# ELEC70101_TempSensors.net
KiCad netlist of a schematic drawn in EasyEDA Pro
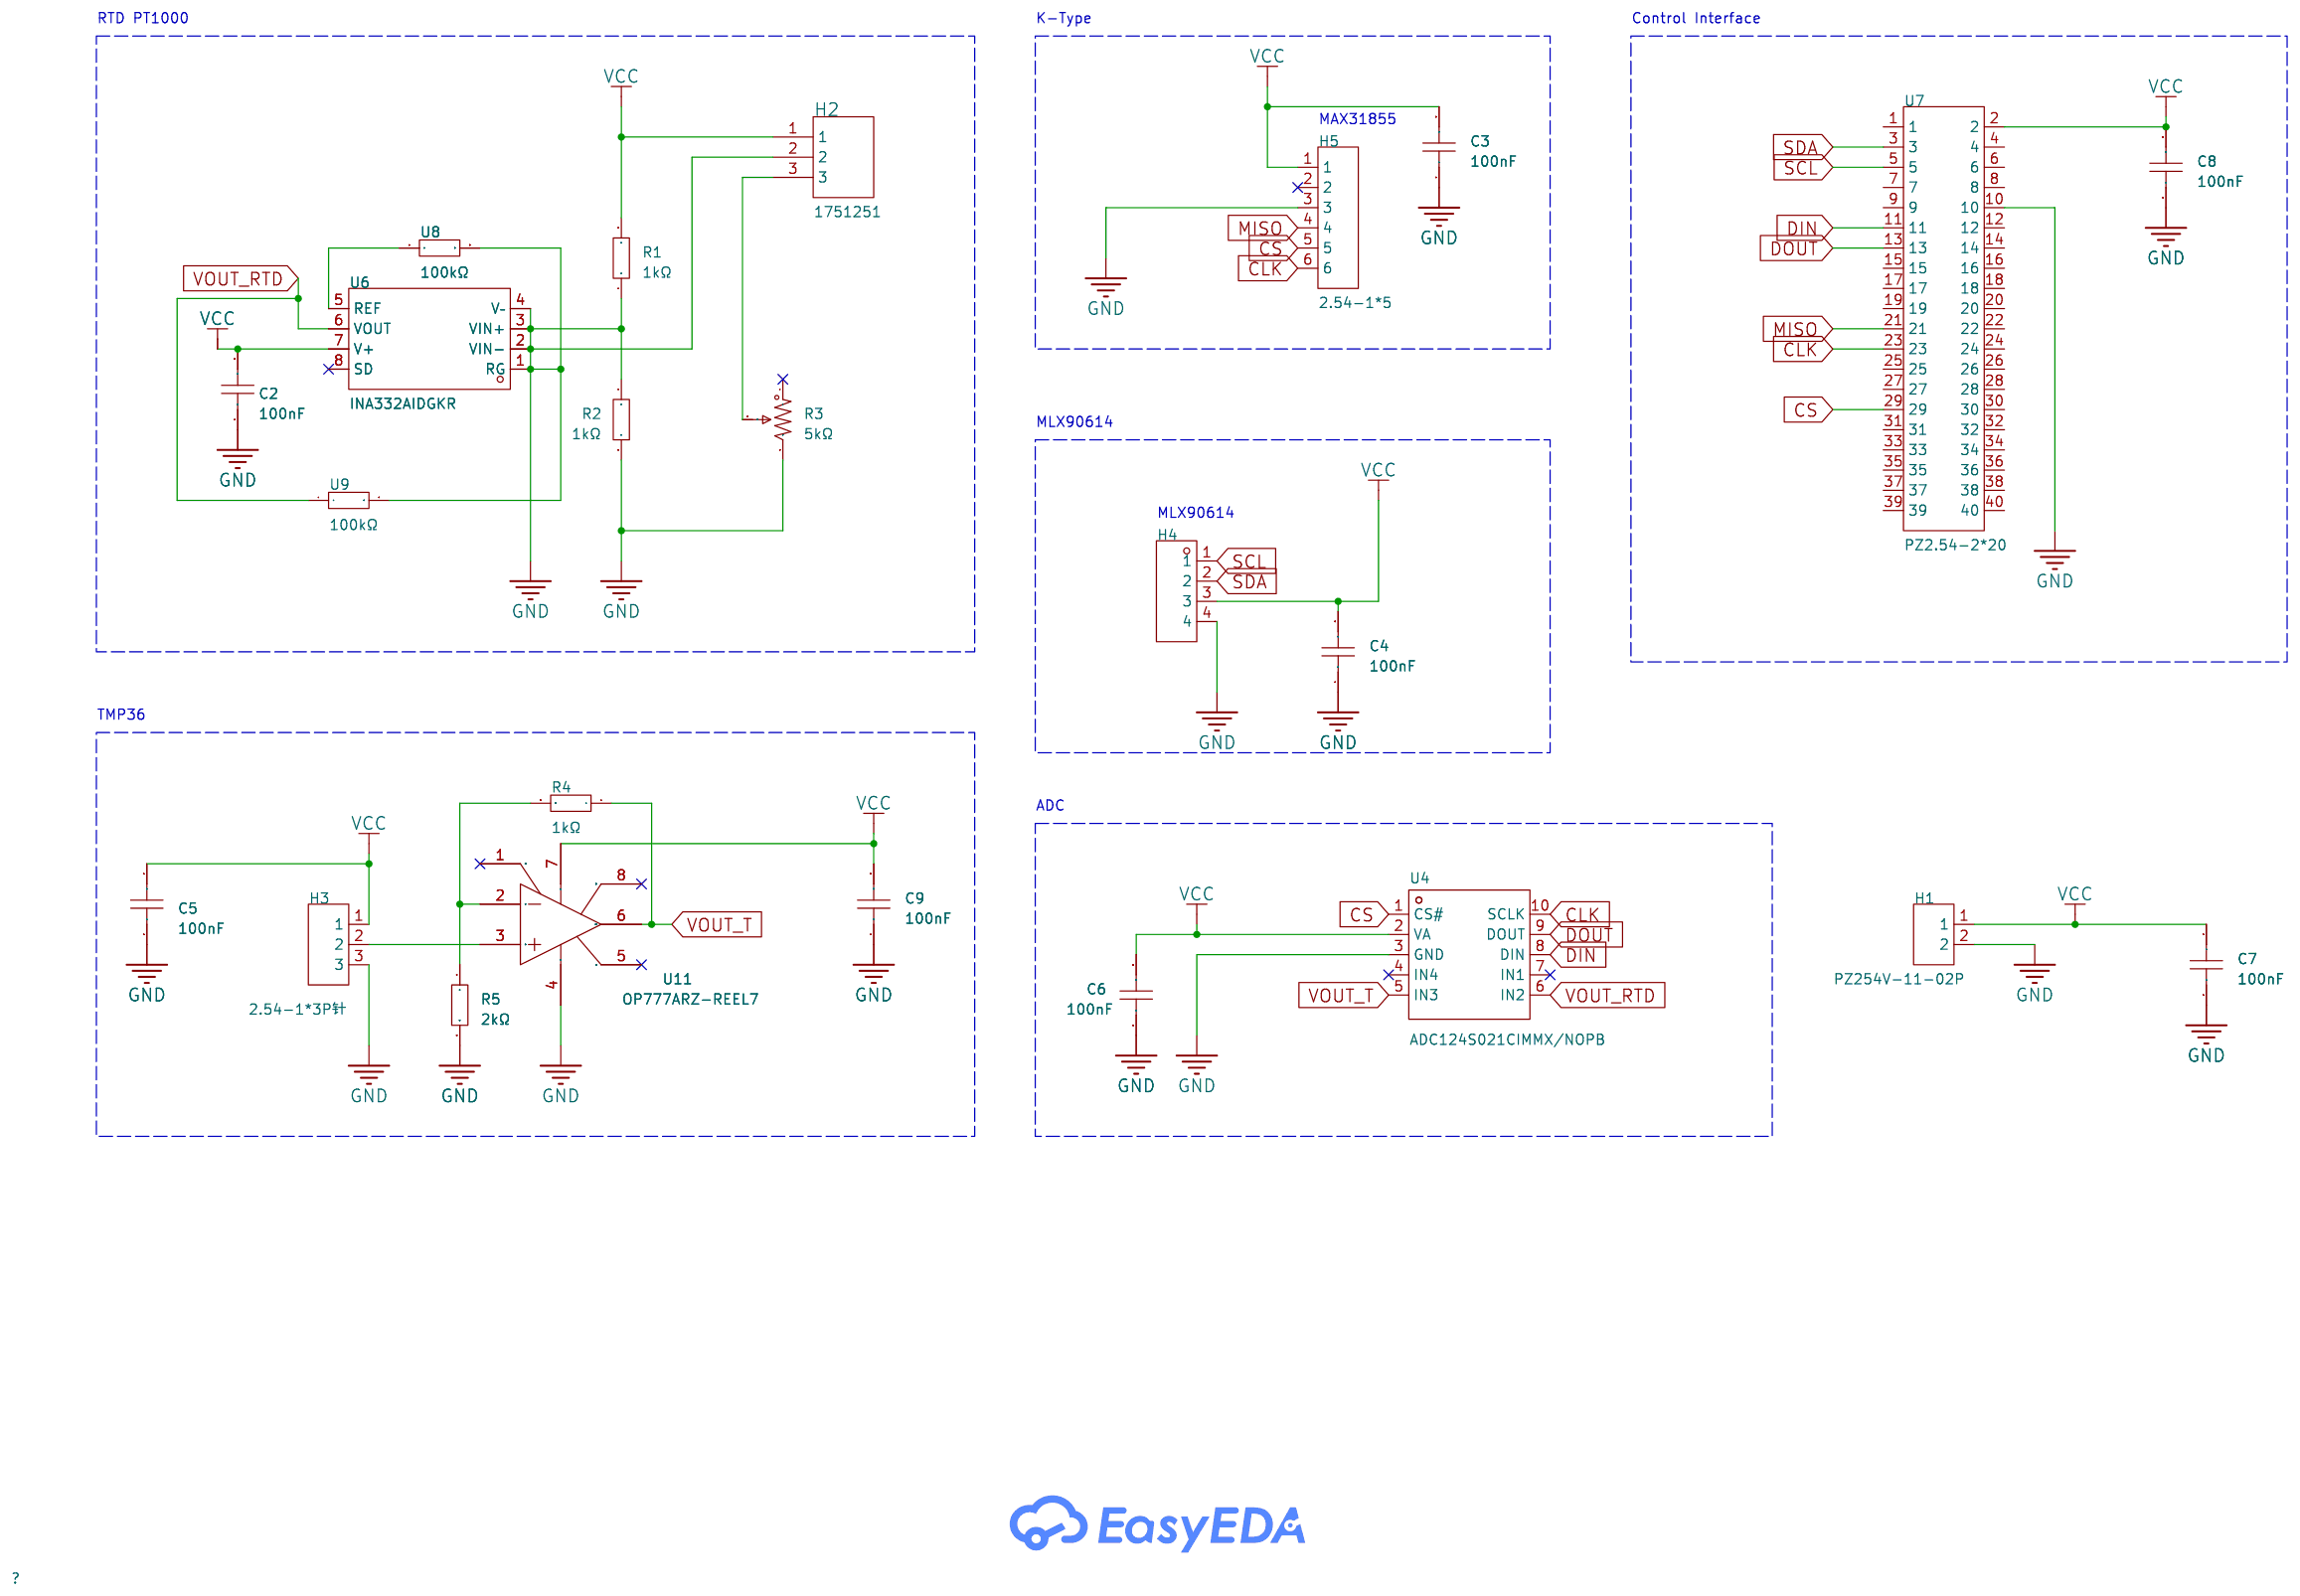
[diagram p0: schematic sheet]

(export (version "E")
  (design (tool "Eeschema 10.0.6"))
  (components
    (comp (ref "C2")
      (value "100nF")
      (footprint "easyedapro:C0805")
      (description "Capacitance:100nF Tolerance:±10% Tolerance:±10% Voltage Rating:50V Temperature Coefficient:X7R")
      (fields
        (field (name "Manufacturer Part") "CC0805KRX7R9BB104")
        (field (name "Manufacturer") "YAGEO(国巨)")
      )
      (libsource (lib "easyedapro") (part "CT41G-0805-2X1-50V-0.1UF-K(N)"))
    )
    (comp (ref "C3")
      (value "100nF")
      (footprint "easyedapro:C0805")
      (description "Capacitance:100nF Tolerance:±10% Tolerance:±10% Voltage Rating:50V Temperature Coefficient:X7R")
      (fields
        (field (name "Manufacturer Part") "CC0805KRX7R9BB104")
        (field (name "Manufacturer") "YAGEO(国巨)")
      )
      (libsource (lib "easyedapro") (part "CT41G-0805-2X1-50V-0.1UF-K(N)"))
    )
    (comp (ref "C4")
      (value "100nF")
      (footprint "easyedapro:C0805")
      (description "Capacitance:100nF Tolerance:±10% Tolerance:±10% Voltage Rating:50V Temperature Coefficient:X7R")
      (fields
        (field (name "Manufacturer Part") "CC0805KRX7R9BB104")
        (field (name "Manufacturer") "YAGEO(国巨)")
      )
      (libsource (lib "easyedapro") (part "CT41G-0805-2X1-50V-0.1UF-K(N)"))
    )
    (comp (ref "C5")
      (value "100nF")
      (footprint "easyedapro:C0805")
      (description "Capacitance:100nF Tolerance:±10% Tolerance:±10% Voltage Rating:50V Temperature Coefficient:X7R")
      (fields
        (field (name "Manufacturer Part") "CC0805KRX7R9BB104")
        (field (name "Manufacturer") "YAGEO(国巨)")
      )
      (libsource (lib "easyedapro") (part "CT41G-0805-2X1-50V-0.1UF-K(N)"))
    )
    (comp (ref "C6")
      (value "100nF")
      (footprint "easyedapro:C0805")
      (description "Capacitance:100nF Tolerance:±10% Tolerance:±10% Voltage Rating:50V Temperature Coefficient:X7R")
      (fields
        (field (name "Manufacturer Part") "CC0805KRX7R9BB104")
        (field (name "Manufacturer") "YAGEO(国巨)")
      )
      (libsource (lib "easyedapro") (part "CT41G-0805-2X1-50V-0.1UF-K(N)"))
    )
    (comp (ref "C7")
      (value "100nF")
      (footprint "easyedapro:C0805")
      (description "Capacitance:100nF Tolerance:±10% Tolerance:±10% Voltage Rating:50V Temperature Coefficient:X7R")
      (fields
        (field (name "Manufacturer Part") "CC0805KRX7R9BB104")
        (field (name "Manufacturer") "YAGEO(国巨)")
      )
      (libsource (lib "easyedapro") (part "CT41G-0805-2X1-50V-0.1UF-K(N)"))
    )
    (comp (ref "C8")
      (value "100nF")
      (footprint "easyedapro:C0805")
      (description "Capacitance:100nF Tolerance:±10% Tolerance:±10% Voltage Rating:50V Temperature Coefficient:X7R")
      (fields
        (field (name "Manufacturer Part") "CC0805KRX7R9BB104")
        (field (name "Manufacturer") "YAGEO(国巨)")
      )
      (libsource (lib "easyedapro") (part "CT41G-0805-2X1-50V-0.1UF-K(N)"))
    )
    (comp (ref "C9")
      (value "100nF")
      (footprint "easyedapro:C0805")
      (description "Capacitance:100nF Tolerance:±10% Tolerance:±10% Voltage Rating:50V Temperature Coefficient:X7R")
      (fields
        (field (name "Manufacturer Part") "CC0805KRX7R9BB104")
        (field (name "Manufacturer") "YAGEO(国巨)")
      )
      (libsource (lib "easyedapro") (part "CT41G-0805-2X1-50V-0.1UF-K(N)"))
    )
    (comp (ref "H1")
      (value "PZ254V-11-02P")
      (footprint "easyedapro:HDR-TH_HTSW-102-06-L-S")
      (fields (field (name "Manufacturer") "XFCN(兴飞)"))
      (libsource (lib "easyedapro") (part "HTSW-102-06-L-S"))
    )
    (comp (ref "H2")
      (value "1751251")
      (footprint "easyedapro:CONN-TH_3P-P3.50_1751251")
      (fields (field (name "Manufacturer") "Phoenix Contact(菲尼克斯)"))
      (libsource (lib "easyedapro") (part "MKDS1/3-3.5"))
    )
    (comp (ref "H3")
      (value "2.54-1*3P针")
      (footprint "easyedapro:HDR-TH_HTSW-103-05-L-S")
      (fields (field (name "Manufacturer") "BOOMELE(博穆精密)"))
      (libsource (lib "easyedapro") (part "HTSW-103-05-L-S"))
    )
    (comp (ref "H4")
      (value "PZ254V-11-04P")
      (footprint "easyedapro:HDR-TH_4P-P2.54-V-M")
      (fields (field (name "Manufacturer") "XFCN(兴飞)"))
      (libsource (lib "easyedapro") (part "PZ254V-11-04P_C2691448"))
    )
    (comp (ref "H5")
      (value "2.54-1*5")
      (footprint "easyedapro:HDR-TH_6P-P2.54-V-M")
      (fields (field (name "Manufacturer") "ZHOURI(洲日)"))
      (libsource (lib "easyedapro") (part "HX PH254-01-06-Z-L11.5 THROUGH HOLE HEADER"))
    )
    (comp (ref "R1")
      (value "1kΩ")
      (footprint "easyedapro:R0603")
      (fields (field (name "Manufacturer Part") "FCR0603F1K") (field (name "Manufacturer") "VO(翔胜)"))
      (libsource (lib "easyedapro") (part "RC0603FR-07100RL"))
    )
    (comp (ref "R2")
      (value "1kΩ")
      (footprint "easyedapro:R0603")
      (fields (field (name "Manufacturer Part") "FCR0603F1K") (field (name "Manufacturer") "VO(翔胜)"))
      (libsource (lib "easyedapro") (part "RC0603FR-07100RL"))
    )
    (comp (ref "R3")
      (value "5kΩ")
      (footprint "easyedapro:RES-ADJ-TH_3362P")
      (fields (field (name "Manufacturer Part") "3362P-1-502LF") (field (name "Manufacturer") "JIERR(捷而瑞)"))
      (libsource (lib "easyedapro") (part "3362P-1-103_C118956"))
    )
    (comp (ref "R4")
      (value "1kΩ")
      (footprint "easyedapro:R0603")
      (fields (field (name "Manufacturer Part") "FCR0603F1K") (field (name "Manufacturer") "VO(翔胜)"))
      (libsource (lib "easyedapro") (part "RC0603FR-07100RL"))
    )
    (comp (ref "R5")
      (value "2kΩ")
      (footprint "easyedapro:R0603")
      (fields
        (field (name "Manufacturer Part") "0805W8F2001T5E")
        (field (name "Manufacturer") "UNI-ROYAL(厚声)")
      )
      (libsource (lib "easyedapro") (part "RC0603FR-07100RL"))
    )
    (comp (ref "U4")
      (value "ADC124S021CIMMX/NOPB")
      (footprint "easyedapro:VSSOP-10_L3.0-W3.0-P0.50-LS4.9-BL")
      (fields (field (name "Manufacturer") "TI(德州仪器)"))
      (libsource (lib "easyedapro") (part "ADC124S021CIMM/NOPB"))
    )
    (comp (ref "U6")
      (value "INA332AIDGKR")
      (footprint "easyedapro:VSSOP-8_L3.0-W3.0-P0.65-LS5.0-BL")
      (fields (field (name "Manufacturer") "TI(德州仪器)"))
      (libsource (lib "easyedapro") (part "INA332AIDGKR"))
    )
    (comp (ref "U7")
      (value "PZ2.54-2*20")
      (footprint "easyedapro:HDR-TH_40P-P2.54-V-M-R2-C20-S2.54")
      (fields (field (name "Manufacturer") "ZHOURI(洲日)"))
      (libsource (lib "easyedapro") (part "PZ2.54-2*20"))
    )
    (comp (ref "U8")
      (value "100kΩ")
      (footprint "easyedapro:RES-TH_BD5.0-L15.5-P19.50-D0.8")
      (fields (field (name "Manufacturer Part") "FMP300JT-73-100K") (field (name "Manufacturer") "YAGEO(国巨)"))
      (libsource (lib "easyedapro") (part "FMP300JT-73-100K"))
    )
    (comp (ref "U9")
      (value "100kΩ")
      (footprint "easyedapro:RES-TH_BD5.0-L15.5-P19.50-D0.8")
      (fields (field (name "Manufacturer Part") "FMP300JT-73-100K") (field (name "Manufacturer") "YAGEO(国巨)"))
      (libsource (lib "easyedapro") (part "FMP300JT-73-100K"))
    )
    (comp (ref "U11")
      (value "OP777ARZ-REEL7")
      (footprint "easyedapro:SOIC-8_L4.9-W3.9-P1.27-LS6.0-BL")
      (fields (field (name "Manufacturer") "ADI(亚德诺)"))
      (libsource (lib "easyedapro") (part "OP777ARZ-REEL7"))
    )
  )
  (nets
    (net (code "1") (name "CLK") (class "Default")
      (node (ref "H5") (pin "6") (pinfunction "6_6") (pintype "unspecified"))
      (node (ref "U4") (pin "10") (pinfunction "SCLK_10") (pintype "unspecified"))
      (node (ref "U7") (pin "23") (pinfunction "23_23") (pintype "unspecified"))
    )
    (net (code "2") (name "CS") (class "Default")
      (node (ref "H5") (pin "5") (pinfunction "5_5") (pintype "unspecified"))
      (node (ref "U4") (pin "1") (pinfunction "CS#_1") (pintype "unspecified"))
      (node (ref "U7") (pin "29") (pinfunction "29_29") (pintype "unspecified"))
    )
    (net (code "3") (name "DIN") (class "Default")
      (node (ref "U4") (pin "8") (pinfunction "DIN_8") (pintype "unspecified"))
      (node (ref "U7") (pin "11") (pinfunction "11_11") (pintype "unspecified"))
    )
    (net (code "4") (name "DOUT") (class "Default")
      (node (ref "U4") (pin "9") (pinfunction "DOUT_9") (pintype "unspecified"))
      (node (ref "U7") (pin "13") (pinfunction "13_13") (pintype "unspecified"))
    )
    (net (code "5") (name "GND") (class "Default")
      (node (ref "C2") (pin "1") (pinfunction "1_1") (pintype "unspecified"))
      (node (ref "C3") (pin "1") (pinfunction "1_1") (pintype "unspecified"))
      (node (ref "C4") (pin "1") (pinfunction "1_1") (pintype "unspecified"))
      (node (ref "C5") (pin "1") (pinfunction "1_1") (pintype "unspecified"))
      (node (ref "C6") (pin "1") (pinfunction "1_1") (pintype "unspecified"))
      (node (ref "C7") (pin "1") (pinfunction "1_1") (pintype "unspecified"))
      (node (ref "C8") (pin "1") (pinfunction "1_1") (pintype "unspecified"))
      (node (ref "C9") (pin "1") (pinfunction "1_1") (pintype "unspecified"))
      (node (ref "H1") (pin "2") (pinfunction "2_2") (pintype "unspecified"))
      (node (ref "H2") (pin "2") (pinfunction "2_2") (pintype "input"))
      (node (ref "H3") (pin "3") (pinfunction "3_3") (pintype "unspecified"))
      (node (ref "H4") (pin "4") (pinfunction "4_4") (pintype "input"))
      (node (ref "H5") (pin "3") (pinfunction "3_3") (pintype "unspecified"))
      (node (ref "R1") (pin "1") (pinfunction "1_1") (pintype "input"))
      (node (ref "R2") (pin "1") (pinfunction "1_1") (pintype "input"))
      (node (ref "R2") (pin "2") (pinfunction "2_2") (pintype "input"))
      (node (ref "R3") (pin "3") (pinfunction "3_3") (pintype "unspecified"))
      (node (ref "R5") (pin "2") (pinfunction "2_2") (pintype "input"))
      (node (ref "U11") (pin "4") (pinfunction "V-_4") (pintype "unspecified"))
      (node (ref "U4") (pin "3") (pinfunction "GND_3") (pintype "unspecified"))
      (node (ref "U6") (pin "1") (pinfunction "RG_1") (pintype "unspecified"))
      (node (ref "U6") (pin "2") (pinfunction "VIN-_2") (pintype "unspecified"))
      (node (ref "U6") (pin "3") (pinfunction "VIN+_3") (pintype "unspecified"))
      (node (ref "U6") (pin "4") (pinfunction "V–_4") (pintype "unspecified"))
      (node (ref "U7") (pin "10") (pinfunction "10_10") (pintype "unspecified"))
      (node (ref "U8") (pin "2") (pinfunction "2_2") (pintype "unspecified"))
      (node (ref "U9") (pin "2") (pinfunction "2_2") (pintype "unspecified"))
    )
    (net (code "6") (name "MISO") (class "Default")
      (node (ref "H5") (pin "4") (pinfunction "4_4") (pintype "unspecified"))
      (node (ref "U7") (pin "21") (pinfunction "21_21") (pintype "unspecified"))
    )
    (net (code "7") (name "Net-(H2-Pad3)") (class "Default")
      (node (ref "H2") (pin "3") (pinfunction "3_3") (pintype "input"))
      (node (ref "R3") (pin "2") (pinfunction "2_2") (pintype "unspecified"))
    )
    (net (code "8") (name "Net-(U6-REF)") (class "Default")
      (node (ref "U6") (pin "5") (pinfunction "REF_5") (pintype "unspecified"))
      (node (ref "U8") (pin "1") (pinfunction "1_1") (pintype "unspecified"))
    )
    (net (code "9") (name "Net-(U11-IN+)") (class "Default")
      (node (ref "H3") (pin "2") (pinfunction "2_2") (pintype "unspecified"))
      (node (ref "U11") (pin "3") (pinfunction "IN+_3") (pintype "unspecified"))
    )
    (net (code "10") (name "Net-(U11-IN-)") (class "Default")
      (node (ref "R4") (pin "2") (pinfunction "2_2") (pintype "input"))
      (node (ref "R5") (pin "1") (pinfunction "1_1") (pintype "input"))
      (node (ref "U11") (pin "2") (pinfunction "IN-_2") (pintype "unspecified"))
    )
    (net (code "11") (name "SCL") (class "Default")
      (node (ref "H4") (pin "1") (pinfunction "1_1") (pintype "input"))
      (node (ref "U7") (pin "5") (pinfunction "5_5") (pintype "unspecified"))
    )
    (net (code "12") (name "SDA") (class "Default")
      (node (ref "H4") (pin "2") (pinfunction "2_2") (pintype "input"))
      (node (ref "U7") (pin "3") (pinfunction "3_3") (pintype "unspecified"))
    )
    (net (code "13") (name "VCC") (class "Default")
      (node (ref "C2") (pin "2") (pinfunction "2_2") (pintype "unspecified"))
      (node (ref "C3") (pin "2") (pinfunction "2_2") (pintype "unspecified"))
      (node (ref "C4") (pin "2") (pinfunction "2_2") (pintype "unspecified"))
      (node (ref "C5") (pin "2") (pinfunction "2_2") (pintype "unspecified"))
      (node (ref "C6") (pin "2") (pinfunction "2_2") (pintype "unspecified"))
      (node (ref "C7") (pin "2") (pinfunction "2_2") (pintype "unspecified"))
      (node (ref "C8") (pin "2") (pinfunction "2_2") (pintype "unspecified"))
      (node (ref "C9") (pin "2") (pinfunction "2_2") (pintype "unspecified"))
      (node (ref "H1") (pin "1") (pinfunction "1_1") (pintype "unspecified"))
      (node (ref "H2") (pin "1") (pinfunction "1_1") (pintype "input"))
      (node (ref "H3") (pin "1") (pinfunction "1_1") (pintype "unspecified"))
      (node (ref "H4") (pin "3") (pinfunction "3_3") (pintype "input"))
      (node (ref "H5") (pin "1") (pinfunction "1_1") (pintype "unspecified"))
      (node (ref "R1") (pin "2") (pinfunction "2_2") (pintype "input"))
      (node (ref "U11") (pin "7") (pinfunction "V+_7") (pintype "unspecified"))
      (node (ref "U4") (pin "2") (pinfunction "VA_2") (pintype "unspecified"))
      (node (ref "U6") (pin "7") (pinfunction "V+_7") (pintype "unspecified"))
      (node (ref "U7") (pin "2") (pinfunction "2_2") (pintype "unspecified"))
    )
    (net (code "14") (name "VOUT_RTD") (class "Default")
      (node (ref "U4") (pin "6") (pinfunction "IN2_6") (pintype "unspecified"))
      (node (ref "U6") (pin "6") (pinfunction "VOUT_6") (pintype "unspecified"))
      (node (ref "U9") (pin "1") (pinfunction "1_1") (pintype "unspecified"))
    )
    (net (code "15") (name "VOUT_T") (class "Default")
      (node (ref "R4") (pin "1") (pinfunction "1_1") (pintype "input"))
      (node (ref "U11") (pin "6") (pinfunction "OUT_6") (pintype "output"))
      (node (ref "U4") (pin "5") (pinfunction "IN3_5") (pintype "unspecified"))
    )
    (net (code "16") (name "unconnected-(H5-Pad2)") (class "Default")
      (node (ref "H5") (pin "2") (pinfunction "2_2") (pintype "unspecified+no_connect"))
    )
    (net (code "17") (name "unconnected-(R3-Pad1)") (class "Default")
      (node (ref "R3") (pin "1") (pinfunction "1_1") (pintype "unspecified+no_connect"))
    )
    (net (code "18") (name "unconnected-(U4-IN1-Pad7)") (class "Default")
      (node (ref "U4") (pin "7") (pinfunction "IN1_7") (pintype "unspecified+no_connect"))
    )
    (net (code "19") (name "unconnected-(U4-IN4-Pad4)") (class "Default")
      (node (ref "U4") (pin "4") (pinfunction "IN4_4") (pintype "unspecified+no_connect"))
    )
    (net (code "20") (name "unconnected-(U6-SD-Pad8)") (class "Default")
      (node (ref "U6") (pin "8") (pinfunction "SD_8") (pintype "unspecified+no_connect"))
    )
    (net (code "21") (name "unconnected-(U7-Pad1)") (class "Default")
      (node (ref "U7") (pin "1") (pinfunction "1_1") (pintype "unspecified"))
    )
    (net (code "22") (name "unconnected-(U7-Pad4)") (class "Default")
      (node (ref "U7") (pin "4") (pinfunction "4_4") (pintype "unspecified"))
    )
    (net (code "23") (name "unconnected-(U7-Pad6)") (class "Default")
      (node (ref "U7") (pin "6") (pinfunction "6_6") (pintype "unspecified"))
    )
    (net (code "24") (name "unconnected-(U7-Pad7)") (class "Default")
      (node (ref "U7") (pin "7") (pinfunction "7_7") (pintype "unspecified"))
    )
    (net (code "25") (name "unconnected-(U7-Pad8)") (class "Default")
      (node (ref "U7") (pin "8") (pinfunction "8_8") (pintype "unspecified"))
    )
    (net (code "26") (name "unconnected-(U7-Pad9)") (class "Default")
      (node (ref "U7") (pin "9") (pinfunction "9_9") (pintype "unspecified"))
    )
    (net (code "27") (name "unconnected-(U7-Pad12)") (class "Default")
      (node (ref "U7") (pin "12") (pinfunction "12_12") (pintype "unspecified"))
    )
    (net (code "28") (name "unconnected-(U7-Pad14)") (class "Default")
      (node (ref "U7") (pin "14") (pinfunction "14_14") (pintype "unspecified"))
    )
    (net (code "29") (name "unconnected-(U7-Pad15)") (class "Default")
      (node (ref "U7") (pin "15") (pinfunction "15_15") (pintype "unspecified"))
    )
    (net (code "30") (name "unconnected-(U7-Pad16)") (class "Default")
      (node (ref "U7") (pin "16") (pinfunction "16_16") (pintype "unspecified"))
    )
    (net (code "31") (name "unconnected-(U7-Pad17)") (class "Default")
      (node (ref "U7") (pin "17") (pinfunction "17_17") (pintype "unspecified"))
    )
    (net (code "32") (name "unconnected-(U7-Pad18)") (class "Default")
      (node (ref "U7") (pin "18") (pinfunction "18_18") (pintype "unspecified"))
    )
    (net (code "33") (name "unconnected-(U7-Pad19)") (class "Default")
      (node (ref "U7") (pin "19") (pinfunction "19_19") (pintype "unspecified"))
    )
    (net (code "34") (name "unconnected-(U7-Pad20)") (class "Default")
      (node (ref "U7") (pin "20") (pinfunction "20_20") (pintype "unspecified"))
    )
    (net (code "35") (name "unconnected-(U7-Pad22)") (class "Default")
      (node (ref "U7") (pin "22") (pinfunction "22_22") (pintype "unspecified"))
    )
    (net (code "36") (name "unconnected-(U7-Pad24)") (class "Default")
      (node (ref "U7") (pin "24") (pinfunction "24_24") (pintype "unspecified"))
    )
    (net (code "37") (name "unconnected-(U7-Pad25)") (class "Default")
      (node (ref "U7") (pin "25") (pinfunction "25_25") (pintype "unspecified"))
    )
    (net (code "38") (name "unconnected-(U7-Pad26)") (class "Default")
      (node (ref "U7") (pin "26") (pinfunction "26_26") (pintype "unspecified"))
    )
    (net (code "39") (name "unconnected-(U7-Pad27)") (class "Default")
      (node (ref "U7") (pin "27") (pinfunction "27_27") (pintype "unspecified"))
    )
    (net (code "40") (name "unconnected-(U7-Pad28)") (class "Default")
      (node (ref "U7") (pin "28") (pinfunction "28_28") (pintype "unspecified"))
    )
    (net (code "41") (name "unconnected-(U7-Pad30)") (class "Default")
      (node (ref "U7") (pin "30") (pinfunction "30_30") (pintype "unspecified"))
    )
    (net (code "42") (name "unconnected-(U7-Pad31)") (class "Default")
      (node (ref "U7") (pin "31") (pinfunction "31_31") (pintype "unspecified"))
    )
    (net (code "43") (name "unconnected-(U7-Pad32)") (class "Default")
      (node (ref "U7") (pin "32") (pinfunction "32_32") (pintype "unspecified"))
    )
    (net (code "44") (name "unconnected-(U7-Pad33)") (class "Default")
      (node (ref "U7") (pin "33") (pinfunction "33_33") (pintype "unspecified"))
    )
    (net (code "45") (name "unconnected-(U7-Pad34)") (class "Default")
      (node (ref "U7") (pin "34") (pinfunction "34_34") (pintype "unspecified"))
    )
    (net (code "46") (name "unconnected-(U7-Pad35)") (class "Default")
      (node (ref "U7") (pin "35") (pinfunction "35_35") (pintype "unspecified"))
    )
    (net (code "47") (name "unconnected-(U7-Pad36)") (class "Default")
      (node (ref "U7") (pin "36") (pinfunction "36_36") (pintype "unspecified"))
    )
    (net (code "48") (name "unconnected-(U7-Pad37)") (class "Default")
      (node (ref "U7") (pin "37") (pinfunction "37_37") (pintype "unspecified"))
    )
    (net (code "49") (name "unconnected-(U7-Pad38)") (class "Default")
      (node (ref "U7") (pin "38") (pinfunction "38_38") (pintype "unspecified"))
    )
    (net (code "50") (name "unconnected-(U7-Pad39)") (class "Default")
      (node (ref "U7") (pin "39") (pinfunction "39_39") (pintype "unspecified"))
    )
    (net (code "51") (name "unconnected-(U7-Pad40)") (class "Default")
      (node (ref "U7") (pin "40") (pinfunction "40_40") (pintype "unspecified"))
    )
    (net (code "52") (name "unconnected-(U11-NC-Pad1)") (class "Default")
      (node (ref "U11") (pin "1") (pinfunction "NC_1") (pintype "unspecified+no_connect"))
    )
    (net (code "53") (name "unconnected-(U11-NC-Pad5)") (class "Default")
      (node (ref "U11") (pin "5") (pinfunction "NC_5") (pintype "unspecified+no_connect"))
    )
    (net (code "54") (name "unconnected-(U11-NC-Pad8)") (class "Default")
      (node (ref "U11") (pin "8") (pinfunction "NC_8") (pintype "unspecified+no_connect"))
    )
  )
)
